# Power.net
KiCad netlist of a schematic drawn in Altium Designer
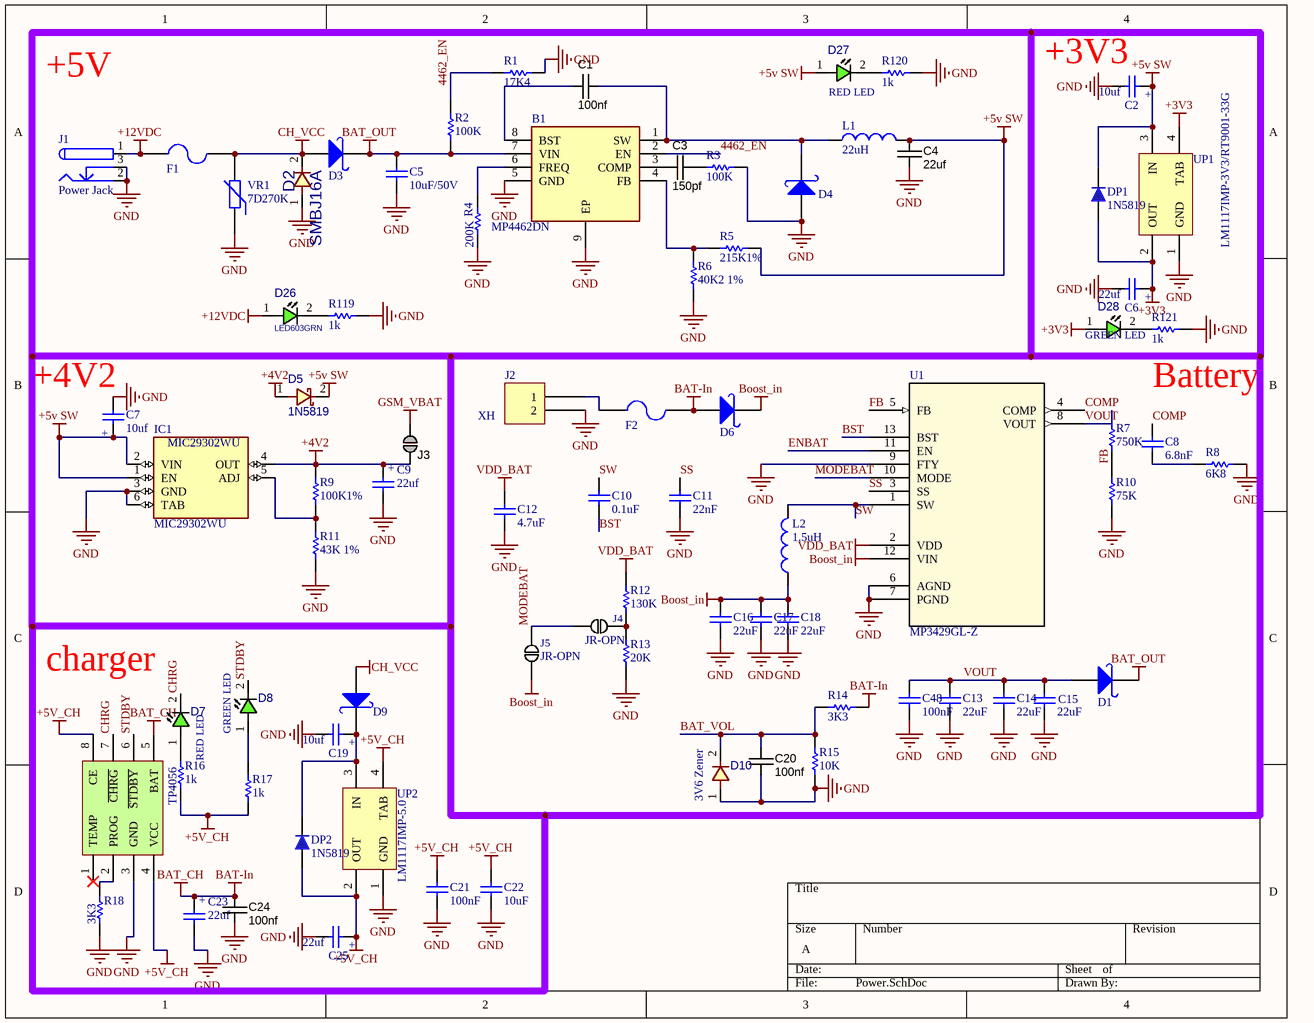
[diagram p0: Power.SchDoc]

(export (version "E")
  (design (tool "Eeschema 10.0.6"))
  (components
    (comp (ref "B1")
      (value "MP4462DN")
      (footprint "SOIC127P600X170-9N")
      (description "Power Supply")
      (fields (field (name "MANUFACTURER_PART_NUMBER") "MP4462DN-Z-LF"))
      (libsource (lib "altium-import") (part "root_0_mirrored_MP4462DN-Z-LF_"))
    )
    (comp (ref "C1")
      (value "100nf")
      (footprint "CAPC1608X90N")
      (description "Capacitor C SMD 0603")
      (fields (field (name "TOLERANCE") "±10%"))
      (libsource (lib "altium-import") (part "root_1_CAPC_100n_0603_X7R_50V_10%_"))
    )
    (comp (ref "C2")
      (value "10uf")
      (footprint "MY_CAP_SMD-A")
      (description "Capacitor Tantalum SMD")
      (libsource (lib "altium-import") (part "root_2_CAP_TANTAL_A_"))
    )
    (comp (ref "C3")
      (value "150pf")
      (footprint "CAPC1608X90N")
      (description "Capacitor C SMD 0603")
      (fields (field (name "TOLERANCE") "±10%"))
      (libsource (lib "altium-import") (part "root_1_CAPC_100n_0603_X7R_50V_10%_"))
    )
    (comp (ref "C4")
      (value "22uf")
      (footprint "CAPC1608X90N")
      (description "Capacitor C SMD 1206")
      (fields (field (name "TOLERANCE") "±10%"))
      (libsource (lib "altium-import") (part "root_2_CAPC_100n_0603_X7R_50V_10%_"))
    )
    (comp (ref "C5")
      (value "10uF/50V")
      (description "Capacitor C SMD 1206")
      (libsource (lib "2017AbbasBasereh9365731239 -ver1") (part "CAP SMD 0805"))
    )
    (comp (ref "C6")
      (value "22uf")
      (footprint "MY_CAP_SMD-A")
      (description "Capacitor Tantalum SMD")
      (libsource (lib "altium-import") (part "root_2_CAP_TANTAL_A_"))
    )
    (comp (ref "C7")
      (value "10uf")
      (footprint "MY_CAP_SMD-A")
      (description "Capacitor Tantalum SMD")
      (libsource (lib "altium-import") (part "root_1_CAP_TANTAL_A_"))
    )
    (comp (ref "C8")
      (value "6.8nF")
      (footprint "CAPC3413X12N")
      (description "Capacitor C SMD 0603")
      (fields (field (name "DESIGNER") "Abbas Basereh"))
      (libsource (lib "2017AbbasBasereh9365731239 -ver1") (part "CAP SMD 0805"))
    )
    (comp (ref "C9")
      (value "22uf")
      (footprint "MY_CAP_SMD-A")
      (description "Capacitor Tantalum SMD")
      (libsource (lib "altium-import") (part "root_3_CAP_TANTAL_A_"))
    )
    (comp (ref "C10")
      (value "0.1uF")
      (footprint "CAPC3413X12N")
      (description "CAP 0805")
      (fields (field (name "DESIGNER") "Abbas Basereh"))
      (libsource (lib "2017AbbasBasereh9365731239 -ver1") (part "CAP SMD 0805"))
    )
    (comp (ref "C11")
      (value "22nF")
      (footprint "CAPC3413X12N")
      (description "CAP 0805")
      (fields (field (name "DESIGNER") "Abbas Basereh"))
      (libsource (lib "2017AbbasBasereh9365731239 -ver1") (part "CAP SMD 0805"))
    )
    (comp (ref "C12")
      (value "4.7uF")
      (footprint "CAPC3413X12N")
      (description "CAP 0805")
      (fields (field (name "DESIGNER") "Abbas Basereh"))
      (libsource (lib "2017AbbasBasereh9365731239 -ver1") (part "CAP SMD 0805"))
    )
    (comp (ref "C13")
      (value "22uF")
      (footprint "CAPC3413X12N")
      (description "CAP 0805")
      (fields (field (name "DESIGNER") "Abbas Basereh"))
      (libsource (lib "2017AbbasBasereh9365731239 -ver1") (part "CAP SMD 0805"))
    )
    (comp (ref "C14")
      (value "22uF")
      (footprint "CAPC3413X12N")
      (description "CAP 0805")
      (fields (field (name "DESIGNER") "Abbas Basereh"))
      (libsource (lib "2017AbbasBasereh9365731239 -ver1") (part "CAP SMD 0805"))
    )
    (comp (ref "C15")
      (value "22uF")
      (footprint "CAPC3413X12N")
      (description "CAP 0805")
      (fields (field (name "DESIGNER") "Abbas Basereh"))
      (libsource (lib "2017AbbasBasereh9365731239 -ver1") (part "CAP SMD 0805"))
    )
    (comp (ref "C16")
      (value "22uF")
      (footprint "CAPC3413X12N")
      (description "Capacitor C SMD 0805")
      (fields (field (name "DESIGNER") "Abbas Basereh"))
      (libsource (lib "2017AbbasBasereh9365731239 -ver1") (part "CAP SMD 0805"))
    )
    (comp (ref "C17")
      (value "22uF")
      (footprint "CAPC3413X12N")
      (description "Capacitor C SMD 0805")
      (fields (field (name "DESIGNER") "Abbas Basereh"))
      (libsource (lib "2017AbbasBasereh9365731239 -ver1") (part "CAP SMD 0805"))
    )
    (comp (ref "C18")
      (value "22uF")
      (footprint "CAPC3413X12N")
      (description "CAP 0805")
      (fields (field (name "DESIGNER") "Abbas Basereh"))
      (libsource (lib "2017AbbasBasereh9365731239 -ver1") (part "CAP SMD 0805"))
    )
    (comp (ref "C19")
      (value "10uf")
      (footprint "MY_CAP_SMD-A")
      (description "3.2X1.6MM")
      (libsource (lib "altium-import") (part "root_2_CAP_TANTAL_A_"))
    )
    (comp (ref "C20")
      (value "100nf")
      (footprint "CAPC1608X90N")
      (description "Capacitor SMD Cer 100nF 10% 50V X7R 0603")
      (fields (field (name "TOLERANCE") "±10%"))
      (libsource (lib "altium-import") (part "root_0_CAPC_100n_0603_X7R_50V_10%_"))
    )
    (comp (ref "C21")
      (value "100nF")
      (footprint "CAPC3413X12N")
      (description "CAP 0805")
      (fields (field (name "DESIGNER") "Abbas Basereh"))
      (libsource (lib "2017AbbasBasereh9365731239 -ver1") (part "CAP SMD 0805"))
    )
    (comp (ref "C22")
      (value "10uF")
      (footprint "CAPC3413X12N")
      (description "CAP 0805")
      (fields (field (name "DESIGNER") "Abbas Basereh"))
      (libsource (lib "2017AbbasBasereh9365731239 -ver1") (part "CAP SMD 0805"))
    )
    (comp (ref "C23")
      (value "22uf")
      (footprint "MY_CAP_SMD-A")
      (description "Capacitor Tantalum SMD")
      (libsource (lib "altium-import") (part "root_3_CAP_TANTAL_A_"))
    )
    (comp (ref "C24")
      (value "100nf")
      (footprint "CAPC1608X90N")
      (description "Capacitor SMD Cer 100nF 10% 50V X7R 0603")
      (fields (field (name "TOLERANCE") "±10%"))
      (libsource (lib "altium-import") (part "root_0_CAPC_100n_0603_X7R_50V_10%_"))
    )
    (comp (ref "C25")
      (value "22uf")
      (footprint "MY_CAP_SMD-A")
      (description "3.2X1.6MM")
      (libsource (lib "altium-import") (part "root_2_CAP_TANTAL_A_"))
    )
    (comp (ref "C48")
      (value "100nF")
      (footprint "CAPC3413X12N")
      (description "CAP 0805")
      (fields (field (name "DESIGNER") "Abbas Basereh"))
      (libsource (lib "2017AbbasBasereh9365731239 -ver1") (part "CAP SMD 0805"))
    )
    (comp (ref "D1")
      (value "1n5822")
      (footprint "DO-214AB(SMC)")
      (description "Schottky Rectifiers")
      (fields
        (field (name "MANUFACTURER") "ON Semiconductor/Fairchild")
        (field (name "DESIGNER") "Abbas Basereh")
      )
      (libsource (lib "altium-import") (part "root_0_1n5822 SMD_"))
    )
    (comp (ref "D2")
      (value "SMBJ16A")
      (footprint "DO214AA SMB")
      (description "TVS Surface Mount Transient Voltage Suppressors Diode")
      (fields (field (name "Comment") "SMBJ16A-TR"))
      (libsource (lib "Diode") (part "SMBJ12A-TR"))
    )
    (comp (ref "D3")
      (value "1n5822")
      (footprint "DO-214AB(SMC)")
      (description "Schottky Rectifiers")
      (fields
        (field (name "MANUFACTURER") "ON Semiconductor/Fairchild")
        (field (name "DESIGNER") "Abbas Basereh")
      )
      (libsource (lib "altium-import") (part "root_0_1n5822 SMD_"))
    )
    (comp (ref "D4")
      (value "1n5822")
      (footprint "DO-214AB(SMC)")
      (description "Schottky Rectifiers")
      (fields
        (field (name "MANUFACTURER") "ON Semiconductor/Fairchild")
        (field (name "DESIGNER") "Abbas Basereh")
      )
      (libsource (lib "altium-import") (part "root_1_1n5822 SMD_"))
    )
    (comp (ref "D5")
      (value "1N5819")
      (footprint "D_SOD123W")
      (description "DIODE, GENERAL PURPOSE, 1000V/1A")
      (fields (field (name "MANF") "DIODES") (field (name "MANF_P#") "1N5819HW-7-F"))
      (libsource (lib "pouria lib2") (part "DIODE_SMD_SCHOTTKY_1N5819"))
    )
    (comp (ref "D6")
      (value "1n5822")
      (footprint "DO-214AB(SMC)")
      (description "Schottky Rectifiers")
      (fields
        (field (name "MANUFACTURER") "ON Semiconductor/Fairchild")
        (field (name "DESIGNER") "Abbas Basereh")
      )
      (libsource (lib "altium-import") (part "root_0_1n5822 SMD_"))
    )
    (comp (ref "D7")
      (value "RED LED")
      (footprint "LED0603GRN")
      (description "LED, SMD, 0603, GREEN")
      (fields (field (name "MANF") "Kingbright") (field (name "MANF_P#") "APT1608SGC"))
      (libsource (lib "led(diode)") (part "LED_SMD_0603_GRN"))
    )
    (comp (ref "D8")
      (value "GREEN LED")
      (footprint "LED0603GRN")
      (description "LED, SMD, 0603, GREEN")
      (fields (field (name "MANF") "Kingbright") (field (name "MANF_P#") "APT1608SGC"))
      (libsource (lib "led(diode)") (part "LED_SMD_0603_GRN"))
    )
    (comp (ref "D9")
      (value "1n5822")
      (footprint "DO-214AB(SMC)")
      (description "Schottky Rectifiers")
      (fields
        (field (name "MANUFACTURER") "ON Semiconductor/Fairchild")
        (field (name "DESIGNER") "Abbas Basereh")
      )
      (libsource (lib "altium-import") (part "root_3_1n5822 SMD_"))
    )
    (comp (ref "D10")
      (value "3V6 Zener")
      (footprint "D_SOD80")
      (description "DIODE, FAST SWTICHING, 0.3A, 0.5W")
      (fields (field (name "Comment") "5Z1"))
      (libsource (lib "Diode") (part "1N4148 SMD"))
    )
    (comp (ref "D26")
      (value "LED603GRN")
      (footprint "LED0603GRN")
      (description "LED, SMD, 0603, GREEN")
      (fields (field (name "MANF") "Kingbright") (field (name "MANF_P#") "APT1608SGC"))
      (libsource (lib "led(diode)") (part "LED_SMD_0603_GRN"))
    )
    (comp (ref "D27")
      (value "RED LED")
      (footprint "LED0603GRN")
      (description "LED, SMD, 0603, GREEN")
      (fields (field (name "MANF") "Kingbright") (field (name "MANF_P#") "APT1608SGC"))
      (libsource (lib "led(diode)") (part "LED_SMD_0603_GRN"))
    )
    (comp (ref "D28")
      (value "GREEN LED")
      (footprint "LED0603GRN")
      (description "LED, SMD, 0603, GREEN")
      (fields (field (name "MANF") "Kingbright") (field (name "MANF_P#") "APT1608SGC"))
      (libsource (lib "led(diode)") (part "LED_SMD_0603_GRN"))
    )
    (comp (ref "DP1")
      (value "1N5819")
      (footprint "430X270D")
      (description "DIODE, GENERAL PURPOSE, 1000V/1A")
      (fields (field (name "DESIGNER") "Abbas Basereh"))
      (libsource (lib "2017AbbasBasereh9365731239 -ver1") (part "1N5819"))
    )
    (comp (ref "DP2")
      (value "1N5819")
      (footprint "430X270D")
      (description "Schottkey Rectifiers")
      (fields (field (name "DESIGNER") "Abbas Basereh"))
      (libsource (lib "2017AbbasBasereh9365731239 -ver1") (part "1N5819"))
    )
    (comp (ref "F1")
      (value "FUSE Socket")
      (footprint "Crystal SMD")
      (description "SMD Fuses 1808")
      (fields (field (name "DESIGNER") "Abbas Basereh"))
      (libsource (lib "2017AbbasBasereh9365731239 -ver1") (part "Fuse SMD1206"))
    )
    (comp (ref "F2")
      (value "FUSE Socket")
      (description "SMD Fuses 1808")
      (fields (field (name "DESIGNER") "Abbas Basereh"))
      (libsource (lib "2017AbbasBasereh9365731239 -ver1") (part "Fuse SMD1206"))
    )
    (comp (ref "IC1")
      (value "MIC29302WU")
      (footprint "MIC29302WU:TO263-5")
      (description "Linear Voltage Regulator IC 1 Output 3A TO-263-5")
      (fields (field (name "MF") "{'manufacturer': u'Microchip Technology'}"))
      (libsource (lib "altium-import") (part "root_0_MIC29302WU_"))
    )
    (comp (ref "J1")
      (value "Power Jack")
      (footprint "Power Jack")
      (libsource (lib "altium-import") (part "root_0_Power Jack_"))
    )
    (comp (ref "J2")
      (value "XH")
      (footprint "JST XH B2B-XH-A")
      (description "CONN HEADER VERT 2POS 2.5MM XH")
      (fields
        (field (name "PART NUMBER") "B2B-XH-A(LF)(SN)")
        (field (name "MANUFACTURER") "JST Sales America Inc.")
      )
      (libsource (lib "Connectors - Rectangular Headers Male Pins") (part "B2B-XH-A(LF)(SN)"))
    )
    (comp (ref "J3")
      (value "Jumper")
      (footprint "JUMP1")
      (description "SMD jumper")
      (libsource (lib "Utiliti_Library") (part "JUMP1"))
    )
    (comp (ref "J4") (value "JR-OPN") (description "SOLDERDOT BYPASS") (libsource (lib "*") (part "BYPASS")))
    (comp (ref "J5") (value "JR-OPN") (description "SOLDERDOT BYPASS") (libsource (lib "*") (part "BYPASS")))
    (comp (ref "L1")
      (value "22uH")
      (footprint "INDUCTOR_SMD_3A")
      (libsource (lib "altium-import") (part "root_0_INDUCTOR_SMD_3A_"))
    )
    (comp (ref "L2")
      (value "1.5uH")
      (footprint "INDUCTOR_SMD_3A")
      (libsource (lib "altium-import") (part "root_1_INDUCTOR_SMD_3A_"))
    )
    (comp (ref "R1")
      (value "17K4")
      (footprint "Resistor_SMD_0603 (1608)")
      (description "Resistor SMD 0805")
      (fields (field (name "PUBLISHER") "Seyed Razi Vesali") (field (name "EMAIL") "razi.vesali@gmail.com"))
      (libsource (lib "resistors") (part "Resistor"))
    )
    (comp (ref "R2")
      (value "100K")
      (footprint "Resistor_SMD_0603 (1608)")
      (description "Resistor SMD 0603")
      (fields (field (name "PUBLISHER") "Seyed Razi Vesali") (field (name "EMAIL") "razi.vesali@gmail.com"))
      (libsource (lib "resistors") (part "Resistor"))
    )
    (comp (ref "R3")
      (value "100K")
      (footprint "Resistor_SMD_0603 (1608)")
      (description "Resistor SMD 0603")
      (fields (field (name "PUBLISHER") "Seyed Razi Vesali") (field (name "EMAIL") "razi.vesali@gmail.com"))
      (libsource (lib "resistors") (part "Resistor"))
    )
    (comp (ref "R4")
      (value "200K")
      (footprint "Resistor_SMD_0603 (1608)")
      (description "Resistor SMD 0603")
      (fields (field (name "PUBLISHER") "Seyed Razi Vesali") (field (name "EMAIL") "razi.vesali@gmail.com"))
      (libsource (lib "resistors") (part "Resistor"))
    )
    (comp (ref "R5")
      (value "215K1%")
      (footprint "Resistor_SMD_0603 (1608)")
      (description "Resistor SMD 0805")
      (fields (field (name "PUBLISHER") "Seyed Razi Vesali") (field (name "EMAIL") "razi.vesali@gmail.com"))
      (libsource (lib "resistors") (part "Resistor"))
    )
    (comp (ref "R6")
      (value "40K2 1%")
      (footprint "Resistor_SMD_0603 (1608)")
      (description "Resistor SMD 0603")
      (fields (field (name "PUBLISHER") "Seyed Razi Vesali") (field (name "EMAIL") "razi.vesali@gmail.com"))
      (libsource (lib "resistors") (part "Resistor"))
    )
    (comp (ref "R7")
      (value "750K")
      (footprint "Resistor_SMD_0603 (1608)")
      (description "Resistor 0603")
      (fields (field (name "PUBLISHER") "Seyed Razi Vesali") (field (name "EMAIL") "razi.vesali@gmail.com"))
      (libsource (lib "resistors") (part "Resistor"))
    )
    (comp (ref "R8")
      (value "6K8")
      (footprint "Resistor_SMD_0603 (1608)")
      (description "Resistor 0603")
      (fields (field (name "PUBLISHER") "Seyed Razi Vesali") (field (name "EMAIL") "razi.vesali@gmail.com"))
      (libsource (lib "resistors") (part "Resistor"))
    )
    (comp (ref "R9")
      (value "100K1%")
      (footprint "Resistor_SMD_0603 (1608)")
      (description "Resistor 0603")
      (fields (field (name "PUBLISHER") "Seyed Razi Vesali") (field (name "EMAIL") "razi.vesali@gmail.com"))
      (libsource (lib "resistors") (part "Resistor"))
    )
    (comp (ref "R10")
      (value "75K")
      (footprint "Resistor_SMD_0603 (1608)")
      (description "Resistor 0603")
      (fields (field (name "PUBLISHER") "Seyed Razi Vesali") (field (name "EMAIL") "razi.vesali@gmail.com"))
      (libsource (lib "resistors") (part "Resistor"))
    )
    (comp (ref "R11")
      (value "43K 1%")
      (footprint "Resistor_SMD_0603 (1608)")
      (description "Resistor 0603")
      (fields (field (name "PUBLISHER") "Seyed Razi Vesali") (field (name "EMAIL") "razi.vesali@gmail.com"))
      (libsource (lib "resistors") (part "Resistor"))
    )
    (comp (ref "R12")
      (value "130K")
      (footprint "Resistor_SMD_0603 (1608)")
      (description "Resistor0603")
      (fields (field (name "PUBLISHER") "Seyed Razi Vesali") (field (name "EMAIL") "razi.vesali@gmail.com"))
      (libsource (lib "resistors") (part "Resistor"))
    )
    (comp (ref "R13")
      (value "20K")
      (footprint "Resistor_SMD_0603 (1608)")
      (description "Resistor 0603")
      (fields (field (name "PUBLISHER") "Seyed Razi Vesali") (field (name "EMAIL") "razi.vesali@gmail.com"))
      (libsource (lib "resistors") (part "Resistor"))
    )
    (comp (ref "R14")
      (value "3K3")
      (footprint "Resistor_SMD_0603 (1608)")
      (description "Resistor 0603")
      (fields (field (name "PUBLISHER") "Seyed Razi Vesali") (field (name "EMAIL") "razi.vesali@gmail.com"))
      (libsource (lib "resistors") (part "Resistor"))
    )
    (comp (ref "R15")
      (value "10K")
      (footprint "Resistor_SMD_0603 (1608)")
      (description "Resistor 0603")
      (fields (field (name "PUBLISHER") "Seyed Razi Vesali") (field (name "EMAIL") "razi.vesali@gmail.com"))
      (libsource (lib "resistors") (part "Resistor"))
    )
    (comp (ref "R16")
      (value "1k")
      (footprint "Resistor_SMD_0603 (1608)")
      (description "Resistor0603")
      (fields (field (name "PUBLISHER") "Seyed Razi Vesali") (field (name "EMAIL") "razi.vesali@gmail.com"))
      (libsource (lib "resistors") (part "Resistor"))
    )
    (comp (ref "R17")
      (value "1k")
      (footprint "Resistor_SMD_0603 (1608)")
      (description "Resistor 0603")
      (fields (field (name "PUBLISHER") "Seyed Razi Vesali") (field (name "EMAIL") "razi.vesali@gmail.com"))
      (libsource (lib "resistors") (part "Resistor"))
    )
    (comp (ref "R18")
      (value "3K3")
      (footprint "Resistor_SMD_0603 (1608)")
      (description "Resistor 0603")
      (fields (field (name "PUBLISHER") "Seyed Razi Vesali") (field (name "EMAIL") "razi.vesali@gmail.com"))
      (libsource (lib "resistors") (part "Resistor"))
    )
    (comp (ref "R119")
      (value "1k")
      (footprint "Resistor_SMD_0603 (1608)")
      (description "Resistor")
      (fields (field (name "PUBLISHER") "Seyed Razi Vesali") (field (name "EMAIL") "razi.vesali@gmail.com"))
      (libsource (lib "resistors") (part "Resistor"))
    )
    (comp (ref "R120")
      (value "1k")
      (footprint "Resistor_SMD_0603 (1608)")
      (description "Resistor 0603")
      (fields (field (name "PUBLISHER") "Seyed Razi Vesali") (field (name "EMAIL") "razi.vesali@gmail.com"))
      (libsource (lib "resistors") (part "Resistor"))
    )
    (comp (ref "R121")
      (value "1k")
      (footprint "Resistor_SMD_0603 (1608)")
      (description "Resistor 0603")
      (fields (field (name "PUBLISHER") "Seyed Razi Vesali") (field (name "EMAIL") "razi.vesali@gmail.com"))
      (libsource (lib "resistors") (part "Resistor"))
    )
    (comp (ref "TP4056")
      (value "TP4056")
      (footprint "TP4056")
      (libsource (lib "altium-import") (part "root_1_TP4056_"))
    )
    (comp (ref "U1")
      (value "MP3429GL-Z")
      (footprint "QFN-3x4_MP3429_MNP")
      (description "No Description Available")
      (fields (field (name "COPYRIGHT") "Copyright (C) 2022 Ultra Librarian. All rights reserved."))
      (libsource (lib "altium-import") (part "root_0_MP3429GL-Z_"))
    )
    (comp (ref "UP1")
      (value "LM1117IMP-3V3/RT9001-33G")
      (footprint "SOT223_M")
      (description "x.x Volt, 800mA Low-Dropout Linear Regulator, 4-pin SOT-223")
      (fields (field (name "DESIGNER") "Ali Hafizi"))
      (libsource (lib "altium-import") (part "root_3_mirrored_AMS1117-x.x_"))
    )
    (comp (ref "UP2")
      (value "LM1117IMP-5.0")
      (footprint "SOT223_M")
      (description "x.x Volt, 800mA Low-Dropout Linear Regulator, 4-pin SOT-223")
      (fields (field (name "DESIGNER") "Ali Hafizi"))
      (libsource (lib "altium-import") (part "root_3_mirrored_AMS1117-x.x_"))
    )
    (comp (ref "VR1")
      (value "7D270K")
      (footprint "05D XXX")
      (description "VARISTORS")
      (fields
        (field (name "MANUFACTURER") "china-canada-philipina")
        (field (name "DESIGNER") "Abbas Basereh")
        (field (name "PUBLISHER") "ABBAS BASEREH")
      )
      (libsource (lib "altium-import") (part "root_1_VARISTOR (VDR)_"))
    )
  )
  (nets
    (net (code "1") (name "+3V3") (class "Default")
      (node (ref "C6") (pin "+") (pinfunction "+_+") (pintype "passive"))
      (node (ref "D28") (pin "1") (pinfunction "ANODE_1") (pintype "passive"))
      (node (ref "DP1") (pin "1") (pintype "passive"))
      (node (ref "UP1") (pin "2") (pinfunction "OUT_2") (pintype "power_in"))
      (node (ref "UP1") (pin "4") (pinfunction "TAB_4") (pintype "power_in"))
    )
    (net (code "2") (name "+4V2") (class "Default")
      (node (ref "C9") (pin "+") (pinfunction "+_+") (pintype "passive"))
      (node (ref "D5") (pin "1") (pinfunction "1_1") (pintype "passive"))
      (node (ref "IC1") (pin "4") (pinfunction "OUT_4") (pintype "bidirectional"))
      (node (ref "J3") (pin "2") (pintype "passive"))
      (node (ref "R9") (pin "2") (pinfunction "2_2") (pintype "passive"))
    )
    (net (code "3") (name "+5V_CH") (class "Default")
      (node (ref "C21") (pin "2") (pinfunction "2_2") (pintype "passive"))
      (node (ref "C22") (pin "2") (pinfunction "2_2") (pintype "passive"))
      (node (ref "C25") (pin "+") (pinfunction "+_+") (pintype "passive"))
      (node (ref "DP2") (pin "1") (pintype "passive"))
      (node (ref "R16") (pin "1") (pinfunction "1_1") (pintype "passive"))
      (node (ref "R17") (pin "1") (pinfunction "1_1") (pintype "passive"))
      (node (ref "TP4056") (pin "4") (pinfunction "VCC_4") (pintype "passive"))
      (node (ref "TP4056") (pin "8") (pinfunction "CE_8") (pintype "passive"))
      (node (ref "UP2") (pin "2") (pinfunction "OUT_2") (pintype "power_in"))
      (node (ref "UP2") (pin "4") (pinfunction "TAB_4") (pintype "power_in"))
    )
    (net (code "4") (name "+5v SW") (class "Default")
      (node (ref "C2") (pin "+") (pinfunction "+_+") (pintype "passive"))
      (node (ref "C4") (pin "2") (pintype "passive"))
      (node (ref "C7") (pin "+") (pinfunction "+_+") (pintype "passive"))
      (node (ref "D27") (pin "1") (pinfunction "ANODE_1") (pintype "passive"))
      (node (ref "D5") (pin "2") (pinfunction "2_2") (pintype "passive"))
      (node (ref "DP1") (pin "2") (pintype "passive"))
      (node (ref "IC1") (pin "1") (pinfunction "EN_1") (pintype "bidirectional"))
      (node (ref "IC1") (pin "2") (pinfunction "VIN_2") (pintype "bidirectional"))
      (node (ref "L1") (pin "2") (pinfunction "2_2") (pintype "passive"))
      (node (ref "R5") (pin "1") (pinfunction "1_1") (pintype "passive"))
      (node (ref "UP1") (pin "3") (pinfunction "IN_3") (pintype "power_in"))
    )
    (net (code "5") (name "+12VDC") (class "Default")
      (node (ref "D26") (pin "1") (pinfunction "ANODE_1") (pintype "passive"))
      (node (ref "F1") (pin "1") (pinfunction "1_1") (pintype "passive"))
      (node (ref "J1") (pin "1") (pinfunction "1_1") (pintype "power_in"))
    )
    (net (code "6") (name "/4462_EN") (class "Default")
      (node (ref "B1") (pin "2") (pinfunction "EN_2") (pintype "passive"))
      (node (ref "R1") (pin "1") (pinfunction "1_1") (pintype "passive"))
      (node (ref "R2") (pin "2") (pinfunction "2_2") (pintype "passive"))
    )
    (net (code "7") (name "/BAT_VOL") (class "Default")
      (node (ref "C20") (pin "1") (pintype "passive"))
      (node (ref "D10") (pin "2") (pinfunction "2_2") (pintype "passive"))
      (node (ref "R14") (pin "1") (pinfunction "1_1") (pintype "passive"))
      (node (ref "R15") (pin "2") (pinfunction "2_2") (pintype "passive"))
    )
    (net (code "8") (name "/BST") (class "Default")
      (node (ref "C10") (pin "1") (pinfunction "1_1") (pintype "passive"))
      (node (ref "U1") (pin "13") (pinfunction "BST_13") (pintype "passive"))
    )
    (net (code "9") (name "/CHRG") (class "Default")
      (node (ref "D7") (pin "2") (pinfunction "CATHODE_2") (pintype "passive"))
      (node (ref "TP4056") (pin "7") (pinfunction "~{CHRG}_7") (pintype "passive"))
    )
    (net (code "10") (name "/COMP") (class "Default")
      (node (ref "C8") (pin "2") (pinfunction "2_2") (pintype "passive"))
      (node (ref "U1") (pin "4") (pinfunction "COMP_4") (pintype "output"))
    )
    (net (code "11") (name "/ENBAT") (class "Default")
      (node (ref "U1") (pin "11") (pinfunction "EN_11") (pintype "passive"))
    )
    (net (code "12") (name "/FB") (class "Default")
      (node (ref "R10") (pin "2") (pinfunction "2_2") (pintype "passive"))
      (node (ref "R7") (pin "1") (pinfunction "1_1") (pintype "passive"))
      (node (ref "U1") (pin "5") (pinfunction "FB_5") (pintype "input"))
    )
    (net (code "13") (name "/MODEBAT") (class "Default")
      (node (ref "J4") (pin "2") (pinfunction "2_2") (pintype "passive"))
      (node (ref "J5") (pin "1") (pinfunction "1_1") (pintype "passive"))
      (node (ref "U1") (pin "10") (pinfunction "MODE_10") (pintype "passive"))
    )
    (net (code "14") (name "/SS") (class "Default")
      (node (ref "C11") (pin "2") (pinfunction "2_2") (pintype "passive"))
      (node (ref "U1") (pin "3") (pinfunction "SS_3") (pintype "passive"))
    )
    (net (code "15") (name "/STDBY") (class "Default")
      (node (ref "D8") (pin "2") (pinfunction "CATHODE_2") (pintype "passive"))
      (node (ref "TP4056") (pin "6") (pinfunction "~{STDBY}_6") (pintype "passive"))
    )
    (net (code "16") (name "/SW") (class "Default")
      (node (ref "C10") (pin "2") (pinfunction "2_2") (pintype "passive"))
      (node (ref "L2") (pin "2") (pinfunction "2_2") (pintype "passive"))
      (node (ref "U1") (pin "1") (pinfunction "SW_1") (pintype "passive"))
    )
    (net (code "17") (name "/VOUT") (class "Default")
      (node (ref "C13") (pin "2") (pinfunction "2_2") (pintype "passive"))
      (node (ref "C14") (pin "2") (pinfunction "2_2") (pintype "passive"))
      (node (ref "C15") (pin "2") (pinfunction "2_2") (pintype "passive"))
      (node (ref "C48") (pin "2") (pinfunction "2_2") (pintype "passive"))
      (node (ref "D1") (pin "1") (pinfunction "A_1") (pintype "passive"))
      (node (ref "R7") (pin "2") (pinfunction "2_2") (pintype "passive"))
      (node (ref "U1") (pin "8") (pinfunction "VOUT_8") (pintype "output"))
    )
    (net (code "18") (name "BAT-In") (class "Default")
      (node (ref "C23") (pin "+") (pinfunction "+_+") (pintype "passive"))
      (node (ref "C24") (pin "1") (pintype "passive"))
      (node (ref "D6") (pin "1") (pinfunction "A_1") (pintype "passive"))
      (node (ref "F2") (pin "2") (pinfunction "2_2") (pintype "passive"))
      (node (ref "R14") (pin "2") (pinfunction "2_2") (pintype "passive"))
      (node (ref "TP4056") (pin "5") (pinfunction "BAT_5") (pintype "passive"))
    )
    (net (code "19") (name "BAT_OUT") (class "Default")
      (node (ref "B1") (pin "7") (pinfunction "VIN_7") (pintype "passive"))
      (node (ref "C5") (pin "2") (pinfunction "2_2") (pintype "passive"))
      (node (ref "D1") (pin "2") (pinfunction "K_2") (pintype "passive"))
      (node (ref "D3") (pin "2") (pinfunction "K_2") (pintype "passive"))
      (node (ref "R2") (pin "1") (pinfunction "1_1") (pintype "passive"))
    )
    (net (code "20") (name "Boost_in") (class "Default")
      (node (ref "C16") (pin "2") (pinfunction "2_2") (pintype "passive"))
      (node (ref "C17") (pin "2") (pinfunction "2_2") (pintype "passive"))
      (node (ref "C18") (pin "2") (pinfunction "2_2") (pintype "passive"))
      (node (ref "D6") (pin "2") (pinfunction "K_2") (pintype "passive"))
      (node (ref "J5") (pin "2") (pinfunction "2_2") (pintype "passive"))
      (node (ref "L2") (pin "1") (pinfunction "1_1") (pintype "passive"))
      (node (ref "U1") (pin "12") (pinfunction "VIN_12") (pintype "power_in"))
    )
    (net (code "21") (name "CH_VCC") (class "Default")
      (node (ref "D2") (pin "2") (pinfunction "2_2") (pintype "passive"))
      (node (ref "D3") (pin "1") (pinfunction "A_1") (pintype "passive"))
      (node (ref "D9") (pin "1") (pinfunction "A_1") (pintype "passive"))
      (node (ref "F1") (pin "2") (pinfunction "2_2") (pintype "passive"))
      (node (ref "VR1") (pin "2") (pinfunction "2_2") (pintype "passive"))
    )
    (net (code "22") (name "GND") (class "Default")
      (node (ref "B1") (pin "5") (pinfunction "GND_5") (pintype "passive"))
      (node (ref "B1") (pin "9") (pinfunction "EP_9") (pintype "passive"))
      (node (ref "C11") (pin "1") (pinfunction "1_1") (pintype "passive"))
      (node (ref "C12") (pin "1") (pinfunction "1_1") (pintype "passive"))
      (node (ref "C13") (pin "1") (pinfunction "1_1") (pintype "passive"))
      (node (ref "C14") (pin "1") (pinfunction "1_1") (pintype "passive"))
      (node (ref "C15") (pin "1") (pinfunction "1_1") (pintype "passive"))
      (node (ref "C16") (pin "1") (pinfunction "1_1") (pintype "passive"))
      (node (ref "C17") (pin "1") (pinfunction "1_1") (pintype "passive"))
      (node (ref "C18") (pin "1") (pinfunction "1_1") (pintype "passive"))
      (node (ref "C19") (pin "-") (pinfunction "-_-") (pintype "passive"))
      (node (ref "C2") (pin "-") (pinfunction "-_-") (pintype "passive"))
      (node (ref "C20") (pin "2") (pintype "passive"))
      (node (ref "C21") (pin "1") (pinfunction "1_1") (pintype "passive"))
      (node (ref "C22") (pin "1") (pinfunction "1_1") (pintype "passive"))
      (node (ref "C23") (pin "-") (pinfunction "-_-") (pintype "passive"))
      (node (ref "C24") (pin "2") (pintype "passive"))
      (node (ref "C25") (pin "-") (pinfunction "-_-") (pintype "passive"))
      (node (ref "C4") (pin "1") (pintype "passive"))
      (node (ref "C48") (pin "1") (pinfunction "1_1") (pintype "passive"))
      (node (ref "C5") (pin "1") (pinfunction "1_1") (pintype "passive"))
      (node (ref "C6") (pin "-") (pinfunction "-_-") (pintype "passive"))
      (node (ref "C7") (pin "-") (pinfunction "-_-") (pintype "passive"))
      (node (ref "C9") (pin "-") (pinfunction "-_-") (pintype "passive"))
      (node (ref "D10") (pin "1") (pinfunction "1_1") (pintype "passive"))
      (node (ref "D2") (pin "1") (pinfunction "1_1") (pintype "passive"))
      (node (ref "D4") (pin "1") (pinfunction "A_1") (pintype "passive"))
      (node (ref "IC1") (pin "3") (pinfunction "GND_3") (pintype "bidirectional"))
      (node (ref "IC1") (pin "6") (pinfunction "TAB_6") (pintype "bidirectional"))
      (node (ref "J1") (pin "2") (pinfunction "2_2") (pintype "power_in"))
      (node (ref "J1") (pin "3") (pinfunction "3_3") (pintype "power_in"))
      (node (ref "J2") (pin "2") (pinfunction "2_2") (pintype "passive"))
      (node (ref "R1") (pin "2") (pinfunction "2_2") (pintype "passive"))
      (node (ref "R10") (pin "1") (pinfunction "1_1") (pintype "passive"))
      (node (ref "R11") (pin "1") (pinfunction "1_1") (pintype "passive"))
      (node (ref "R119") (pin "2") (pinfunction "2_2") (pintype "passive"))
      (node (ref "R120") (pin "2") (pinfunction "2_2") (pintype "passive"))
      (node (ref "R121") (pin "2") (pinfunction "2_2") (pintype "passive"))
      (node (ref "R13") (pin "1") (pinfunction "1_1") (pintype "passive"))
      (node (ref "R15") (pin "1") (pinfunction "1_1") (pintype "passive"))
      (node (ref "R18") (pin "1") (pinfunction "1_1") (pintype "passive"))
      (node (ref "R3") (pin "1") (pinfunction "1_1") (pintype "passive"))
      (node (ref "R4") (pin "2") (pinfunction "2_2") (pintype "passive"))
      (node (ref "R6") (pin "1") (pinfunction "1_1") (pintype "passive"))
      (node (ref "R8") (pin "1") (pinfunction "1_1") (pintype "passive"))
      (node (ref "TP4056") (pin "3") (pinfunction "GND_3") (pintype "passive"))
      (node (ref "U1") (pin "6") (pinfunction "AGND_6") (pintype "passive"))
      (node (ref "U1") (pin "7") (pinfunction "PGND_7") (pintype "passive"))
      (node (ref "U1") (pin "9") (pinfunction "FTY_9") (pintype "passive"))
      (node (ref "UP1") (pin "1") (pinfunction "GND_1") (pintype "power_in"))
      (node (ref "UP2") (pin "1") (pinfunction "GND_1") (pintype "power_in"))
      (node (ref "VR1") (pin "1") (pinfunction "1_1") (pintype "passive"))
    )
    (net (code "23") (name "GSM_VBAT") (class "Default") (node (ref "J3") (pin "1") (pintype "passive")))
    (net (code "24") (name "Net-(B1-BST)") (class "Default")
      (node (ref "B1") (pin "8") (pinfunction "BST_8") (pintype "passive"))
      (node (ref "C1") (pin "1") (pintype "passive"))
    )
    (net (code "25") (name "Net-(B1-COMP)") (class "Default")
      (node (ref "B1") (pin "3") (pinfunction "COMP_3") (pintype "passive"))
      (node (ref "C3") (pin "1") (pintype "passive"))
    )
    (net (code "26") (name "Net-(B1-FB)") (class "Default")
      (node (ref "B1") (pin "4") (pinfunction "FB_4") (pintype "passive"))
      (node (ref "R5") (pin "2") (pinfunction "2_2") (pintype "passive"))
      (node (ref "R6") (pin "2") (pinfunction "2_2") (pintype "passive"))
    )
    (net (code "27") (name "Net-(B1-FREQ)") (class "Default")
      (node (ref "B1") (pin "6") (pinfunction "FREQ_6") (pintype "passive"))
      (node (ref "R4") (pin "1") (pinfunction "1_1") (pintype "passive"))
    )
    (net (code "28") (name "Net-(B1-SW)") (class "Default")
      (node (ref "B1") (pin "1") (pinfunction "SW_1") (pintype "passive"))
      (node (ref "C1") (pin "2") (pintype "passive"))
      (node (ref "D4") (pin "2") (pinfunction "K_2") (pintype "passive"))
      (node (ref "L1") (pin "1") (pinfunction "1_1") (pintype "passive"))
    )
    (net (code "29") (name "Net-(C3-Pad2)") (class "Default")
      (node (ref "C3") (pin "2") (pintype "passive"))
      (node (ref "R3") (pin "2") (pinfunction "2_2") (pintype "passive"))
    )
    (net (code "30") (name "Net-(C8-Pad1)") (class "Default")
      (node (ref "C8") (pin "1") (pinfunction "1_1") (pintype "passive"))
      (node (ref "R8") (pin "2") (pinfunction "2_2") (pintype "passive"))
    )
    (net (code "31") (name "Net-(D7-ANODE)") (class "Default")
      (node (ref "D7") (pin "1") (pinfunction "ANODE_1") (pintype "passive"))
      (node (ref "R16") (pin "2") (pinfunction "2_2") (pintype "passive"))
    )
    (net (code "32") (name "Net-(D8-ANODE)") (class "Default")
      (node (ref "D8") (pin "1") (pinfunction "ANODE_1") (pintype "passive"))
      (node (ref "R17") (pin "2") (pinfunction "2_2") (pintype "passive"))
    )
    (net (code "33") (name "Net-(D9-K)") (class "Default")
      (node (ref "C19") (pin "+") (pinfunction "+_+") (pintype "passive"))
      (node (ref "D9") (pin "2") (pinfunction "K_2") (pintype "passive"))
      (node (ref "DP2") (pin "2") (pintype "passive"))
      (node (ref "UP2") (pin "3") (pinfunction "IN_3") (pintype "power_in"))
    )
    (net (code "34") (name "Net-(D26-CATHODE)") (class "Default")
      (node (ref "D26") (pin "2") (pinfunction "CATHODE_2") (pintype "passive"))
      (node (ref "R119") (pin "1") (pinfunction "1_1") (pintype "passive"))
    )
    (net (code "35") (name "Net-(D27-CATHODE)") (class "Default")
      (node (ref "D27") (pin "2") (pinfunction "CATHODE_2") (pintype "passive"))
      (node (ref "R120") (pin "1") (pinfunction "1_1") (pintype "passive"))
    )
    (net (code "36") (name "Net-(D28-CATHODE)") (class "Default")
      (node (ref "D28") (pin "2") (pinfunction "CATHODE_2") (pintype "passive"))
      (node (ref "R121") (pin "1") (pinfunction "1_1") (pintype "passive"))
    )
    (net (code "37") (name "Net-(F2-Pad1)") (class "Default")
      (node (ref "F2") (pin "1") (pinfunction "1_1") (pintype "passive"))
      (node (ref "J2") (pin "1") (pinfunction "1_1") (pintype "passive"))
    )
    (net (code "38") (name "Net-(IC1-ADJ)") (class "Default")
      (node (ref "IC1") (pin "5") (pinfunction "ADJ_5") (pintype "bidirectional"))
      (node (ref "R11") (pin "2") (pinfunction "2_2") (pintype "passive"))
      (node (ref "R9") (pin "1") (pinfunction "1_1") (pintype "passive"))
    )
    (net (code "39") (name "Net-(J4-Pad1)") (class "Default")
      (node (ref "J4") (pin "1") (pinfunction "1_1") (pintype "passive"))
      (node (ref "R12") (pin "1") (pinfunction "1_1") (pintype "passive"))
      (node (ref "R13") (pin "2") (pinfunction "2_2") (pintype "passive"))
    )
    (net (code "40") (name "Net-(TP4056-PROG)") (class "Default")
      (node (ref "R18") (pin "2") (pinfunction "2_2") (pintype "passive"))
      (node (ref "TP4056") (pin "2") (pinfunction "PROG_2") (pintype "passive"))
    )
    (net (code "41") (name "VDD_BAT") (class "Default")
      (node (ref "C12") (pin "2") (pinfunction "2_2") (pintype "passive"))
      (node (ref "R12") (pin "2") (pinfunction "2_2") (pintype "passive"))
      (node (ref "U1") (pin "2") (pinfunction "VDD_2") (pintype "power_in"))
    )
    (net (code "42") (name "unconnected-(TP4056-TEMP-Pad1)") (class "Default")
      (node (ref "TP4056") (pin "1") (pinfunction "TEMP_1") (pintype "passive+no_connect"))
    )
  )
)
